# Schaltplan.net
KiCad netlist of a schematic drawn in EAGLE
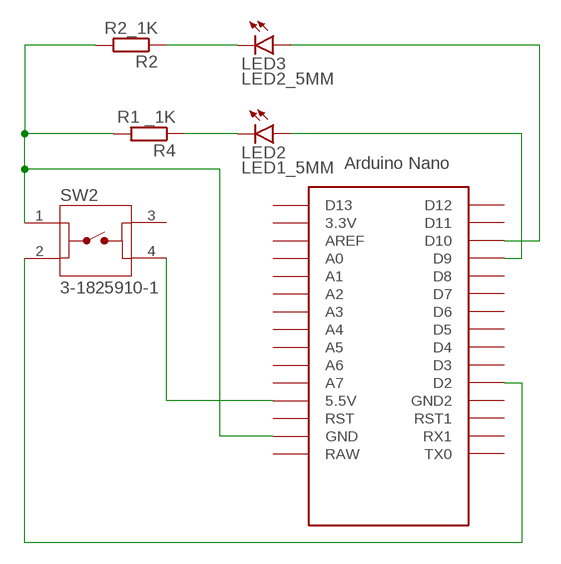
[diagram p0: schematic, sheet 1]

(export (version "E")
  (design (tool "Eeschema 10.0.6"))
  (components
    (comp (ref "LED2")
      (value "LED1_5MM")
      (footprint "eagle-import:P47F-TOP")
      (libsource (lib "eagle-import") (part "P4-TOPLA"))
    )
    (comp (ref "LED3")
      (value "LED2_5MM")
      (footprint "eagle-import:P47F-TOP")
      (libsource (lib "eagle-import") (part "P4-TOPLA"))
    )
    (comp (ref "R2")
      (value "R2_1K")
      (footprint "eagle-import:0207_12")
      (libsource (lib "eagle-import") (part "R-EU_0207/12"))
    )
    (comp (ref "R4")
      (value "R1 _1K")
      (footprint "eagle-import:0207_12")
      (libsource (lib "eagle-import") (part "R-EU_0207/12"))
    )
    (comp (ref "SW2")
      (value "3-1825910-1")
      (footprint "eagle-import:TE_3-1825910-1")
      (fields (field (name "MF") "TE Connectivity"))
      (libsource (lib "eagle-import") (part "3-1825910-1"))
    )
    (comp (ref "U$1")
      (value "NANO")
      (footprint "eagle-import:NANO")
      (libsource (lib "eagle-import") (part "NANO"))
    )
  )
  (nets
    (net (code "1") (name "Net-(LED2-PadA)") (class "Default")
      (node (ref "LED2") (pin "A") (pinfunction "A_A") (pintype "passive"))
      (node (ref "U$1") (pin "D9") (pinfunction "D9_D9") (pintype "bidirectional"))
    )
    (net (code "2") (name "Net-(LED2-PadC)") (class "Default")
      (node (ref "LED2") (pin "C") (pinfunction "C_C") (pintype "passive"))
      (node (ref "R4") (pin "1") (pinfunction "1_1") (pintype "passive"))
    )
    (net (code "3") (name "Net-(LED3-PadA)") (class "Default")
      (node (ref "LED3") (pin "A") (pinfunction "A_A") (pintype "passive"))
      (node (ref "U$1") (pin "D10") (pinfunction "D10_D10") (pintype "bidirectional"))
    )
    (net (code "4") (name "Net-(LED3-PadC)") (class "Default")
      (node (ref "LED3") (pin "C") (pinfunction "C_C") (pintype "passive"))
      (node (ref "R2") (pin "1") (pinfunction "1_1") (pintype "passive"))
    )
    (net (code "5") (name "Net-(R2-Pad2)") (class "Default")
      (node (ref "R2") (pin "2") (pinfunction "2_2") (pintype "passive"))
      (node (ref "R4") (pin "2") (pinfunction "2_2") (pintype "passive"))
      (node (ref "SW2") (pin "1") (pinfunction "1_1") (pintype "passive"))
      (node (ref "U$1") (pin "GND") (pinfunction "GND_GND") (pintype "bidirectional"))
    )
    (net (code "6") (name "Net-(SW2-Pad2)") (class "Default")
      (node (ref "SW2") (pin "2") (pinfunction "2_2") (pintype "passive"))
      (node (ref "U$1") (pin "D2") (pinfunction "D2_D2") (pintype "bidirectional"))
    )
    (net (code "7") (name "Net-(U$1-5.5V)") (class "Default")
      (node (ref "SW2") (pin "4") (pinfunction "4_4") (pintype "passive"))
      (node (ref "U$1") (pin "5V") (pinfunction "5.5V_5V") (pintype "bidirectional"))
    )
    (net (code "8") (name "unconnected-(SW2-Pad3)") (class "Default")
      (node (ref "SW2") (pin "3") (pinfunction "3_3") (pintype "passive"))
    )
    (net (code "9") (name "unconnected-(U$1-GND2-PadGND1)") (class "Default")
      (node (ref "U$1") (pin "GND1") (pinfunction "GND2_GND1") (pintype "bidirectional"))
    )
    (net (code "10") (name "unconnected-(U$1-Pad3.3V)") (class "Default")
      (node (ref "U$1") (pin "3.3V") (pinfunction "3.3V_3.3V") (pintype "bidirectional"))
    )
    (net (code "11") (name "unconnected-(U$1-PadA0)") (class "Default")
      (node (ref "U$1") (pin "A0") (pinfunction "A0_A0") (pintype "bidirectional"))
    )
    (net (code "12") (name "unconnected-(U$1-PadA1)") (class "Default")
      (node (ref "U$1") (pin "A1") (pinfunction "A1_A1") (pintype "bidirectional"))
    )
    (net (code "13") (name "unconnected-(U$1-PadA2)") (class "Default")
      (node (ref "U$1") (pin "A2") (pinfunction "A2_A2") (pintype "bidirectional"))
    )
    (net (code "14") (name "unconnected-(U$1-PadA3)") (class "Default")
      (node (ref "U$1") (pin "A3") (pinfunction "A3_A3") (pintype "bidirectional"))
    )
    (net (code "15") (name "unconnected-(U$1-PadA4)") (class "Default")
      (node (ref "U$1") (pin "A4") (pinfunction "A4_A4") (pintype "bidirectional"))
    )
    (net (code "16") (name "unconnected-(U$1-PadA5)") (class "Default")
      (node (ref "U$1") (pin "A5") (pinfunction "A5_A5") (pintype "bidirectional"))
    )
    (net (code "17") (name "unconnected-(U$1-PadA6)") (class "Default")
      (node (ref "U$1") (pin "A6") (pinfunction "A6_A6") (pintype "bidirectional"))
    )
    (net (code "18") (name "unconnected-(U$1-PadA7)") (class "Default")
      (node (ref "U$1") (pin "A7") (pinfunction "A7_A7") (pintype "bidirectional"))
    )
    (net (code "19") (name "unconnected-(U$1-PadAREF)") (class "Default")
      (node (ref "U$1") (pin "AREF") (pinfunction "AREF_AREF") (pintype "bidirectional"))
    )
    (net (code "20") (name "unconnected-(U$1-PadD3)") (class "Default")
      (node (ref "U$1") (pin "D3") (pinfunction "D3_D3") (pintype "bidirectional"))
    )
    (net (code "21") (name "unconnected-(U$1-PadD4)") (class "Default")
      (node (ref "U$1") (pin "D4") (pinfunction "D4_D4") (pintype "bidirectional"))
    )
    (net (code "22") (name "unconnected-(U$1-PadD5)") (class "Default")
      (node (ref "U$1") (pin "D5") (pinfunction "D5_D5") (pintype "bidirectional"))
    )
    (net (code "23") (name "unconnected-(U$1-PadD6)") (class "Default")
      (node (ref "U$1") (pin "D6") (pinfunction "D6_D6") (pintype "bidirectional"))
    )
    (net (code "24") (name "unconnected-(U$1-PadD7)") (class "Default")
      (node (ref "U$1") (pin "D7") (pinfunction "D7_D7") (pintype "bidirectional"))
    )
    (net (code "25") (name "unconnected-(U$1-PadD8)") (class "Default")
      (node (ref "U$1") (pin "D8") (pinfunction "D8_D8") (pintype "bidirectional"))
    )
    (net (code "26") (name "unconnected-(U$1-PadD11)") (class "Default")
      (node (ref "U$1") (pin "D11") (pinfunction "D11_D11") (pintype "bidirectional"))
    )
    (net (code "27") (name "unconnected-(U$1-PadD12)") (class "Default")
      (node (ref "U$1") (pin "D12") (pinfunction "D12_D12") (pintype "bidirectional"))
    )
    (net (code "28") (name "unconnected-(U$1-PadD13)") (class "Default")
      (node (ref "U$1") (pin "D13") (pinfunction "D13_D13") (pintype "bidirectional"))
    )
    (net (code "29") (name "unconnected-(U$1-PadICSP1)") (class "Default")
      (node (ref "U$1") (pin "ICSP1") (pinfunction "ICSP1_ICSP1") (pintype "bidirectional"))
    )
    (net (code "30") (name "unconnected-(U$1-PadICSP2)") (class "Default")
      (node (ref "U$1") (pin "ICSP2") (pinfunction "ICSP2_ICSP2") (pintype "bidirectional"))
    )
    (net (code "31") (name "unconnected-(U$1-PadICSP3)") (class "Default")
      (node (ref "U$1") (pin "ICSP3") (pinfunction "ICSP3_ICSP3") (pintype "bidirectional"))
    )
    (net (code "32") (name "unconnected-(U$1-PadICSP4)") (class "Default")
      (node (ref "U$1") (pin "ICSP4") (pinfunction "ICSP4_ICSP4") (pintype "bidirectional"))
    )
    (net (code "33") (name "unconnected-(U$1-PadICSP5)") (class "Default")
      (node (ref "U$1") (pin "ICSP5") (pinfunction "ICSP5_ICSP5") (pintype "bidirectional"))
    )
    (net (code "34") (name "unconnected-(U$1-PadICSP6)") (class "Default")
      (node (ref "U$1") (pin "ICSP6") (pinfunction "ICSP6_ICSP6") (pintype "bidirectional"))
    )
    (net (code "35") (name "unconnected-(U$1-PadRAW)") (class "Default")
      (node (ref "U$1") (pin "RAW") (pinfunction "RAW_RAW") (pintype "bidirectional"))
    )
    (net (code "36") (name "unconnected-(U$1-PadRST)") (class "Default")
      (node (ref "U$1") (pin "RST") (pinfunction "RST_RST") (pintype "bidirectional"))
    )
    (net (code "37") (name "unconnected-(U$1-PadRST1)") (class "Default")
      (node (ref "U$1") (pin "RST1") (pinfunction "RST1_RST1") (pintype "bidirectional"))
    )
    (net (code "38") (name "unconnected-(U$1-PadRX1)") (class "Default")
      (node (ref "U$1") (pin "RX1") (pinfunction "RX1_RX1") (pintype "bidirectional"))
    )
    (net (code "39") (name "unconnected-(U$1-PadTX0)") (class "Default")
      (node (ref "U$1") (pin "TX0") (pinfunction "TX0_TX0") (pintype "bidirectional"))
    )
  )
)
